# Ethernet.net
KiCad netlist of a schematic drawn in Altium Designer
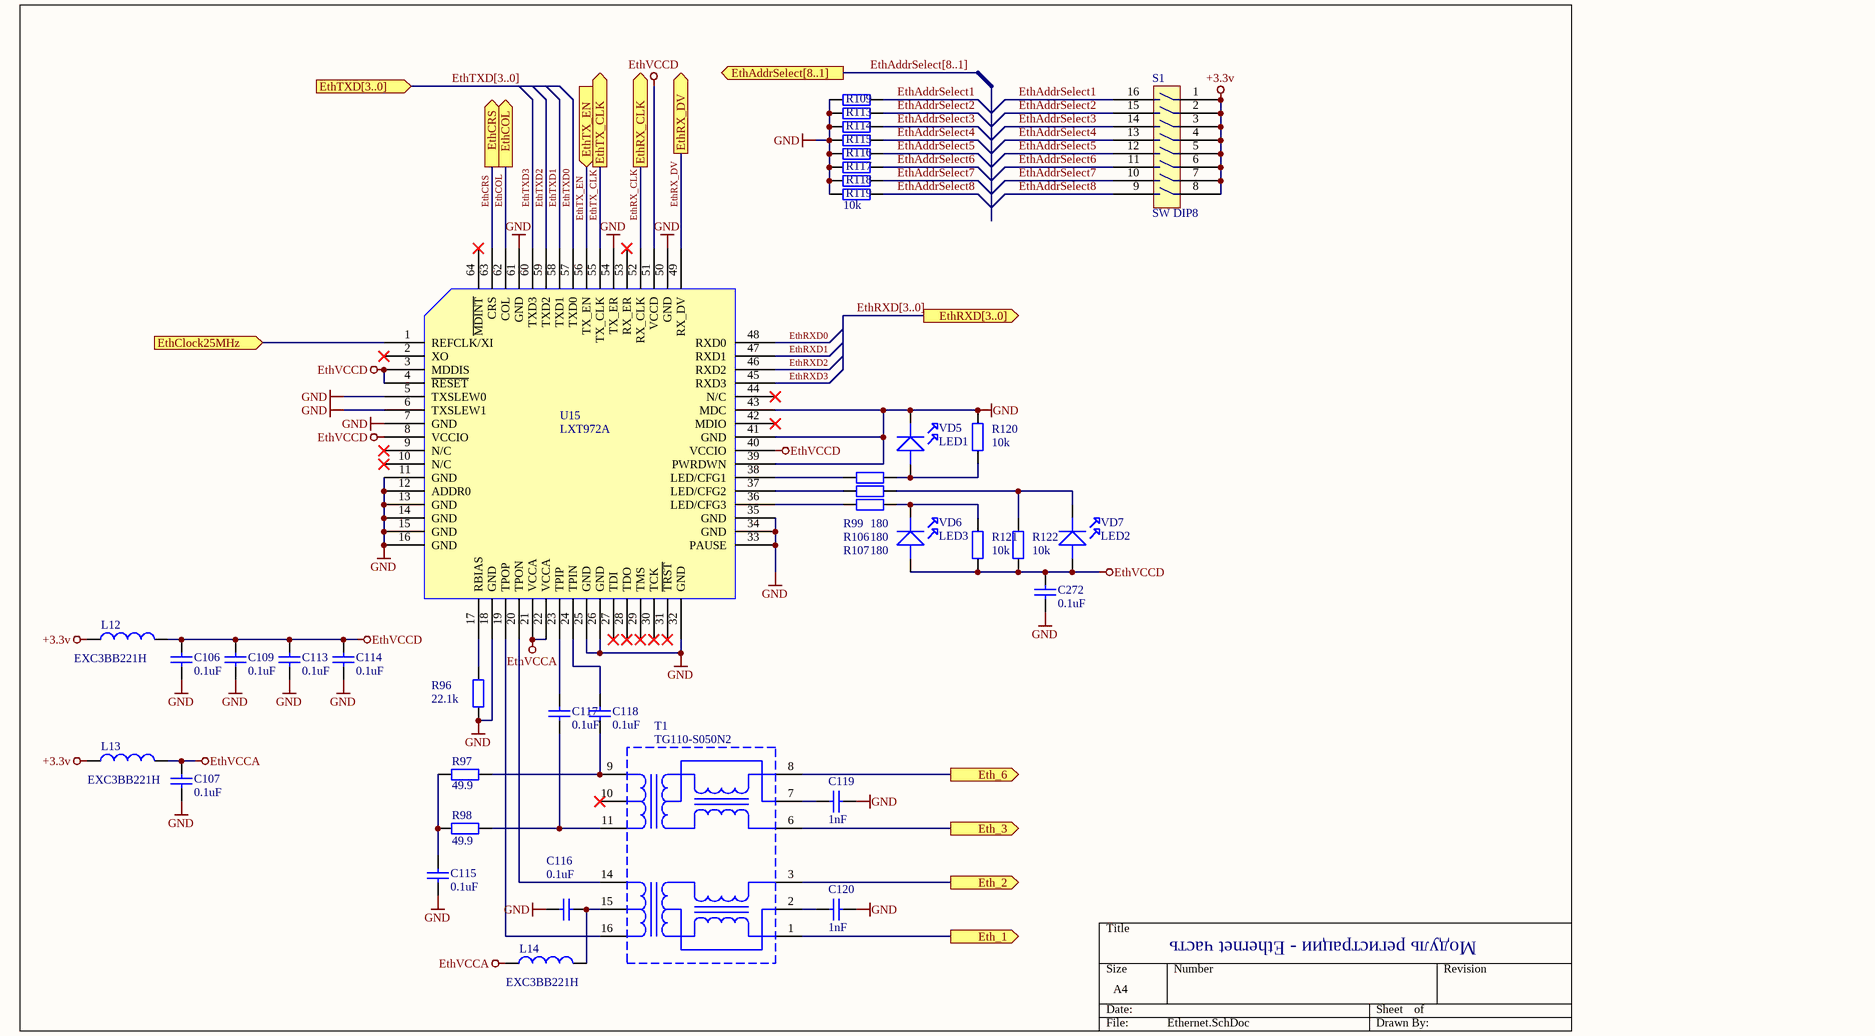
[diagram p0: Ethernet.SchDoc]

(export (version "E")
  (design (tool "Eeschema 10.0.6"))
  (components
    (comp (ref "C106")
      (value "0.1uF")
      (footprint "0603")
      (description "Capacitor")
      (fields (field (name "PUBLISHER") "Altium Limited"))
      (libsource (lib "pcblib1") (part "Cap"))
    )
    (comp (ref "C107")
      (value "0.1uF")
      (footprint "0603")
      (description "Capacitor")
      (fields (field (name "PUBLISHER") "Altium Limited"))
      (libsource (lib "pcblib1") (part "Cap"))
    )
    (comp (ref "C109")
      (value "0.1uF")
      (footprint "0603")
      (description "Capacitor")
      (fields (field (name "PUBLISHER") "Altium Limited"))
      (libsource (lib "pcblib1") (part "Cap"))
    )
    (comp (ref "C113")
      (value "0.1uF")
      (footprint "0603")
      (description "Capacitor")
      (fields (field (name "PUBLISHER") "Altium Limited"))
      (libsource (lib "pcblib1") (part "Cap"))
    )
    (comp (ref "C114")
      (value "0.1uF")
      (footprint "0603")
      (description "Capacitor")
      (fields (field (name "PUBLISHER") "Altium Limited"))
      (libsource (lib "pcblib1") (part "Cap"))
    )
    (comp (ref "C115")
      (value "0.1uF")
      (footprint "0603")
      (description "Capacitor")
      (fields (field (name "PUBLISHER") "Altium Limited"))
      (libsource (lib "pcblib1") (part "Cap"))
    )
    (comp (ref "C116")
      (value "0.1uF")
      (footprint "0603")
      (description "Capacitor")
      (fields (field (name "PUBLISHER") "Altium Limited"))
      (libsource (lib "pcblib1") (part "Cap"))
    )
    (comp (ref "C117")
      (value "0.1uF")
      (footprint "0603")
      (description "Capacitor")
      (fields (field (name "PUBLISHER") "Altium Limited"))
      (libsource (lib "pcblib1") (part "Cap"))
    )
    (comp (ref "C118")
      (value "0.1uF")
      (footprint "0603")
      (description "Capacitor")
      (fields (field (name "PUBLISHER") "Altium Limited"))
      (libsource (lib "pcblib1") (part "Cap"))
    )
    (comp (ref "C119")
      (value "1nF")
      (footprint "0603")
      (description "Capacitor")
      (fields (field (name "PUBLISHER") "Altium Limited"))
      (libsource (lib "pcblib1") (part "Cap"))
    )
    (comp (ref "C120")
      (value "1nF")
      (footprint "0603")
      (description "Capacitor")
      (fields (field (name "PUBLISHER") "Altium Limited"))
      (libsource (lib "pcblib1") (part "Cap"))
    )
    (comp (ref "C272")
      (value "0.1uF")
      (footprint "0603")
      (description "Capacitor")
      (fields (field (name "PUBLISHER") "Altium Limited"))
      (libsource (lib "pcblib1") (part "Cap"))
    )
    (comp (ref "L12") (value "EXC3BB221H") (footprint "0603") (libsource (lib "Adevice") (part "INDUCTOR")))
    (comp (ref "L13") (value "EXC3BB221H") (footprint "0603") (libsource (lib "Adevice") (part "INDUCTOR")))
    (comp (ref "L14") (value "EXC3BB221H") (footprint "0603") (libsource (lib "Adevice") (part "INDUCTOR")))
    (comp (ref "R96")
      (value "22.1k")
      (footprint "0805")
      (description "Resistor")
      (fields (field (name "PUBLISHER") "Altium Limited"))
      (libsource (lib "OD3M") (part "Res2"))
    )
    (comp (ref "R97")
      (value "49.9")
      (footprint "0805")
      (description "Resistor")
      (fields (field (name "PUBLISHER") "Altium Limited"))
      (libsource (lib "") (part "Res2_2"))
    )
    (comp (ref "R98")
      (value "49.9")
      (footprint "0805")
      (description "Resistor")
      (fields (field (name "PUBLISHER") "Altium Limited"))
      (libsource (lib "") (part "Res2_1"))
    )
    (comp (ref "R99")
      (value "180")
      (footprint "0805")
      (description "Resistor")
      (fields (field (name "PUBLISHER") "Altium Limited"))
      (libsource (lib "") (part "Res2_2"))
    )
    (comp (ref "R106")
      (value "180")
      (footprint "0805")
      (description "Resistor")
      (fields (field (name "PUBLISHER") "Altium Limited"))
      (libsource (lib "") (part "Res2_2"))
    )
    (comp (ref "R107")
      (value "180")
      (footprint "0805")
      (description "Resistor")
      (fields (field (name "PUBLISHER") "Altium Limited"))
      (libsource (lib "") (part "Res2_2"))
    )
    (comp (ref "R109")
      (value "10k")
      (footprint "0603")
      (description "Resistor")
      (fields (field (name "PUBLISHER") "Altium Limited"))
      (libsource (lib "") (part "Res2_1"))
    )
    (comp (ref "R113")
      (value "10k")
      (footprint "0603")
      (description "Resistor")
      (fields (field (name "PUBLISHER") "Altium Limited"))
      (libsource (lib "") (part "Res2_1"))
    )
    (comp (ref "R114")
      (value "10k")
      (footprint "0603")
      (description "Resistor")
      (fields (field (name "PUBLISHER") "Altium Limited"))
      (libsource (lib "") (part "Res2_1"))
    )
    (comp (ref "R115")
      (value "10k")
      (footprint "0603")
      (description "Resistor")
      (fields (field (name "PUBLISHER") "Altium Limited"))
      (libsource (lib "") (part "Res2_1"))
    )
    (comp (ref "R116")
      (value "10k")
      (footprint "0603")
      (description "Resistor")
      (fields (field (name "PUBLISHER") "Altium Limited"))
      (libsource (lib "") (part "Res2_1"))
    )
    (comp (ref "R117")
      (value "10k")
      (footprint "0603")
      (description "Resistor")
      (fields (field (name "PUBLISHER") "Altium Limited"))
      (libsource (lib "") (part "Res2_1"))
    )
    (comp (ref "R118")
      (value "10k")
      (footprint "0603")
      (description "Resistor")
      (fields (field (name "PUBLISHER") "Altium Limited"))
      (libsource (lib "") (part "Res2_1"))
    )
    (comp (ref "R119")
      (value "10k")
      (footprint "0603")
      (description "Resistor")
      (fields (field (name "PUBLISHER") "Altium Limited"))
      (libsource (lib "") (part "Res2_1"))
    )
    (comp (ref "R120")
      (value "10k")
      (footprint "0603")
      (description "Resistor")
      (fields (field (name "PUBLISHER") "Altium Limited"))
      (libsource (lib "") (part "Res2_3"))
    )
    (comp (ref "R121")
      (value "10k")
      (footprint "0603")
      (description "Resistor")
      (fields (field (name "PUBLISHER") "Altium Limited"))
      (libsource (lib "") (part "Res2_3"))
    )
    (comp (ref "R122")
      (value "10k")
      (footprint "0603")
      (description "Resistor")
      (fields (field (name "PUBLISHER") "Altium Limited"))
      (libsource (lib "") (part "Res2_3"))
    )
    (comp (ref "S1") (value "SW DIP8") (footprint "SWD4-8") (libsource (lib "Adevice") (part "SW DIP8")))
    (comp (ref "T1")
      (value "TG110-S050N2")
      (footprint "SO-G16/G6.9")
      (libsource (lib "Schlib1") (part "TG110-S050N2"))
    )
    (comp (ref "U15")
      (value "LXT972A")
      (footprint "TQFP64")
      (libsource (lib "MyIntegratedLibrary") (part "LXT972A"))
    )
    (comp (ref "VD5") (value "LED1") (footprint "LED1206") (libsource (lib "Adevice") (part "LED1")))
    (comp (ref "VD6") (value "LED3") (footprint "LED1206") (libsource (lib "Adevice") (part "LED1")))
    (comp (ref "VD7") (value "LED2") (footprint "LED1206") (libsource (lib "Adevice") (part "LED1")))
  )
  (nets
    (net (code "1") (name "+3.3v") (class "Default")
      (node (ref "L12") (pin "1") (pinfunction "1_1") (pintype "passive"))
      (node (ref "L13") (pin "1") (pinfunction "1_1") (pintype "passive"))
      (node (ref "S1") (pin "1") (pinfunction "1_1") (pintype "passive"))
      (node (ref "S1") (pin "2") (pinfunction "2_2") (pintype "passive"))
      (node (ref "S1") (pin "3") (pinfunction "3_3") (pintype "passive"))
      (node (ref "S1") (pin "4") (pinfunction "4_4") (pintype "passive"))
      (node (ref "S1") (pin "5") (pinfunction "5_5") (pintype "passive"))
      (node (ref "S1") (pin "6") (pinfunction "6_6") (pintype "passive"))
      (node (ref "S1") (pin "7") (pinfunction "7_7") (pintype "passive"))
      (node (ref "S1") (pin "8") (pinfunction "8_8") (pintype "passive"))
    )
    (net (code "2") (name "/EthAddrSelect1") (class "Default")
      (node (ref "R109") (pin "1") (pinfunction "1_1") (pintype "passive"))
      (node (ref "S1") (pin "16") (pinfunction "16_16") (pintype "passive"))
    )
    (net (code "3") (name "/EthAddrSelect2") (class "Default")
      (node (ref "R113") (pin "1") (pinfunction "1_1") (pintype "passive"))
      (node (ref "S1") (pin "15") (pinfunction "15_15") (pintype "passive"))
    )
    (net (code "4") (name "/EthAddrSelect3") (class "Default")
      (node (ref "R114") (pin "1") (pinfunction "1_1") (pintype "passive"))
      (node (ref "S1") (pin "14") (pinfunction "14_14") (pintype "passive"))
    )
    (net (code "5") (name "/EthAddrSelect4") (class "Default")
      (node (ref "R115") (pin "1") (pinfunction "1_1") (pintype "passive"))
      (node (ref "S1") (pin "13") (pinfunction "13_13") (pintype "passive"))
    )
    (net (code "6") (name "/EthAddrSelect5") (class "Default")
      (node (ref "R116") (pin "1") (pinfunction "1_1") (pintype "passive"))
      (node (ref "S1") (pin "12") (pinfunction "12_12") (pintype "passive"))
    )
    (net (code "7") (name "/EthAddrSelect6") (class "Default")
      (node (ref "R117") (pin "1") (pinfunction "1_1") (pintype "passive"))
      (node (ref "S1") (pin "11") (pinfunction "11_11") (pintype "passive"))
    )
    (net (code "8") (name "/EthAddrSelect7") (class "Default")
      (node (ref "R118") (pin "1") (pinfunction "1_1") (pintype "passive"))
      (node (ref "S1") (pin "10") (pinfunction "10_10") (pintype "passive"))
    )
    (net (code "9") (name "/EthAddrSelect8") (class "Default")
      (node (ref "R119") (pin "1") (pinfunction "1_1") (pintype "passive"))
      (node (ref "S1") (pin "9") (pinfunction "9_9") (pintype "passive"))
    )
    (net (code "11") (name "/EthCOL") (class "Default")
      (node (ref "U15") (pin "62") (pinfunction "COL_62") (pintype "passive"))
    )
    (net (code "12") (name "/EthCRS") (class "Default")
      (node (ref "U15") (pin "63") (pinfunction "CRS_63") (pintype "passive"))
    )
    (net (code "13") (name "/EthClock25MHz") (class "Default")
      (node (ref "U15") (pin "1") (pinfunction "REFCLK/XI_1") (pintype "passive"))
    )
    (net (code "14") (name "/EthRXD0") (class "Default")
      (node (ref "U15") (pin "48") (pinfunction "RXD0_48") (pintype "passive"))
    )
    (net (code "15") (name "/EthRXD1") (class "Default")
      (node (ref "U15") (pin "47") (pinfunction "RXD1_47") (pintype "passive"))
    )
    (net (code "16") (name "/EthRXD2") (class "Default")
      (node (ref "U15") (pin "46") (pinfunction "RXD2_46") (pintype "passive"))
    )
    (net (code "17") (name "/EthRXD3") (class "Default")
      (node (ref "U15") (pin "45") (pinfunction "RXD3_45") (pintype "passive"))
    )
    (net (code "19") (name "/EthRX_CLK") (class "Default")
      (node (ref "U15") (pin "52") (pinfunction "RX_CLK_52") (pintype "passive"))
    )
    (net (code "20") (name "/EthRX_DV") (class "Default")
      (node (ref "U15") (pin "49") (pinfunction "RX_DV_49") (pintype "passive"))
    )
    (net (code "21") (name "/EthTXD0") (class "Default")
      (node (ref "U15") (pin "57") (pinfunction "TXD0_57") (pintype "passive"))
    )
    (net (code "22") (name "/EthTXD1") (class "Default")
      (node (ref "U15") (pin "58") (pinfunction "TXD1_58") (pintype "passive"))
    )
    (net (code "23") (name "/EthTXD2") (class "Default")
      (node (ref "U15") (pin "59") (pinfunction "TXD2_59") (pintype "passive"))
    )
    (net (code "24") (name "/EthTXD3") (class "Default")
      (node (ref "U15") (pin "60") (pinfunction "TXD3_60") (pintype "passive"))
    )
    (net (code "26") (name "/EthTX_CLK") (class "Default")
      (node (ref "U15") (pin "55") (pinfunction "TX_CLK_55") (pintype "passive"))
    )
    (net (code "27") (name "/EthTX_EN") (class "Default")
      (node (ref "U15") (pin "56") (pinfunction "TX_EN_56") (pintype "passive"))
    )
    (net (code "28") (name "/Eth_1") (class "Default") (node (ref "T1") (pin "1") (pintype "passive")))
    (net (code "29") (name "/Eth_2") (class "Default") (node (ref "T1") (pin "3") (pintype "passive")))
    (net (code "30") (name "/Eth_3") (class "Default") (node (ref "T1") (pin "6") (pintype "passive")))
    (net (code "31") (name "/Eth_6") (class "Default") (node (ref "T1") (pin "8") (pintype "passive")))
    (net (code "32") (name "EthVCCA") (class "Default")
      (node (ref "C107") (pin "2") (pinfunction "2_2") (pintype "passive"))
      (node (ref "L13") (pin "2") (pinfunction "2_2") (pintype "passive"))
      (node (ref "L14") (pin "1") (pinfunction "1_1") (pintype "passive"))
      (node (ref "U15") (pin "21") (pinfunction "VCCA_21") (pintype "passive"))
      (node (ref "U15") (pin "22") (pinfunction "VCCA_22") (pintype "passive"))
    )
    (net (code "33") (name "EthVCCD") (class "Default")
      (node (ref "C106") (pin "2") (pinfunction "2_2") (pintype "passive"))
      (node (ref "C109") (pin "2") (pinfunction "2_2") (pintype "passive"))
      (node (ref "C113") (pin "2") (pinfunction "2_2") (pintype "passive"))
      (node (ref "C114") (pin "2") (pinfunction "2_2") (pintype "passive"))
      (node (ref "C272") (pin "2") (pinfunction "2_2") (pintype "passive"))
      (node (ref "L12") (pin "2") (pinfunction "2_2") (pintype "passive"))
      (node (ref "R121") (pin "1") (pinfunction "1_1") (pintype "passive"))
      (node (ref "R122") (pin "1") (pinfunction "1_1") (pintype "passive"))
      (node (ref "U15") (pin "3") (pinfunction "MDDIS_3") (pintype "passive"))
      (node (ref "U15") (pin "4") (pinfunction "RESET_4") (pintype "passive"))
      (node (ref "U15") (pin "40") (pinfunction "VCCIO_40") (pintype "passive"))
      (node (ref "U15") (pin "51") (pinfunction "VCCD_51") (pintype "passive"))
      (node (ref "U15") (pin "8") (pinfunction "VCCIO_8") (pintype "passive"))
      (node (ref "VD6") (pin "ANODE") (pinfunction "ANODE_ANODE") (pintype "passive"))
      (node (ref "VD7") (pin "ANODE") (pinfunction "ANODE_ANODE") (pintype "passive"))
    )
    (net (code "34") (name "GND") (class "Default")
      (node (ref "C106") (pin "1") (pinfunction "1_1") (pintype "passive"))
      (node (ref "C107") (pin "1") (pinfunction "1_1") (pintype "passive"))
      (node (ref "C109") (pin "1") (pinfunction "1_1") (pintype "passive"))
      (node (ref "C113") (pin "1") (pinfunction "1_1") (pintype "passive"))
      (node (ref "C114") (pin "1") (pinfunction "1_1") (pintype "passive"))
      (node (ref "C115") (pin "2") (pinfunction "2_2") (pintype "passive"))
      (node (ref "C116") (pin "1") (pinfunction "1_1") (pintype "passive"))
      (node (ref "C119") (pin "2") (pinfunction "2_2") (pintype "passive"))
      (node (ref "C120") (pin "1") (pinfunction "1_1") (pintype "passive"))
      (node (ref "C272") (pin "1") (pinfunction "1_1") (pintype "passive"))
      (node (ref "R109") (pin "2") (pinfunction "2_2") (pintype "passive"))
      (node (ref "R113") (pin "2") (pinfunction "2_2") (pintype "passive"))
      (node (ref "R114") (pin "2") (pinfunction "2_2") (pintype "passive"))
      (node (ref "R115") (pin "2") (pinfunction "2_2") (pintype "passive"))
      (node (ref "R116") (pin "2") (pinfunction "2_2") (pintype "passive"))
      (node (ref "R117") (pin "2") (pinfunction "2_2") (pintype "passive"))
      (node (ref "R118") (pin "2") (pinfunction "2_2") (pintype "passive"))
      (node (ref "R119") (pin "2") (pinfunction "2_2") (pintype "passive"))
      (node (ref "R120") (pin "2") (pinfunction "2_2") (pintype "passive"))
      (node (ref "R96") (pin "2") (pinfunction "2_2") (pintype "passive"))
      (node (ref "U15") (pin "11") (pinfunction "GND_11") (pintype "passive"))
      (node (ref "U15") (pin "12") (pinfunction "ADDR0_12") (pintype "passive"))
      (node (ref "U15") (pin "13") (pinfunction "GND_13") (pintype "passive"))
      (node (ref "U15") (pin "14") (pinfunction "GND_14") (pintype "passive"))
      (node (ref "U15") (pin "15") (pinfunction "GND_15") (pintype "passive"))
      (node (ref "U15") (pin "16") (pinfunction "GND_16") (pintype "passive"))
      (node (ref "U15") (pin "18") (pinfunction "GND_18") (pintype "passive"))
      (node (ref "U15") (pin "25") (pinfunction "GND_25") (pintype "passive"))
      (node (ref "U15") (pin "26") (pinfunction "GND_26") (pintype "passive"))
      (node (ref "U15") (pin "32") (pinfunction "GND_32") (pintype "passive"))
      (node (ref "U15") (pin "33") (pinfunction "PAUSE_33") (pintype "passive"))
      (node (ref "U15") (pin "34") (pinfunction "GND_34") (pintype "passive"))
      (node (ref "U15") (pin "35") (pinfunction "GND_35") (pintype "passive"))
      (node (ref "U15") (pin "39") (pinfunction "PWRDWN_39") (pintype "passive"))
      (node (ref "U15") (pin "41") (pinfunction "GND_41") (pintype "passive"))
      (node (ref "U15") (pin "43") (pinfunction "MDC_43") (pintype "passive"))
      (node (ref "U15") (pin "5") (pinfunction "TXSLEW0_5") (pintype "passive"))
      (node (ref "U15") (pin "50") (pinfunction "GND_50") (pintype "passive"))
      (node (ref "U15") (pin "54") (pinfunction "TX_ER_54") (pintype "passive"))
      (node (ref "U15") (pin "6") (pinfunction "TXSLEW1_6") (pintype "passive"))
      (node (ref "U15") (pin "61") (pinfunction "GND_61") (pintype "passive"))
      (node (ref "U15") (pin "7") (pinfunction "GND_7") (pintype "passive"))
      (node (ref "VD5") (pin "CATHODE") (pinfunction "CATHODE_CATHODE") (pintype "passive"))
    )
    (net (code "35") (name "Net-(C115-Pad1)") (class "Default")
      (node (ref "C115") (pin "1") (pinfunction "1_1") (pintype "passive"))
      (node (ref "R97") (pin "1") (pinfunction "1_1") (pintype "passive"))
      (node (ref "R98") (pin "2") (pinfunction "2_2") (pintype "passive"))
    )
    (net (code "36") (name "Net-(C116-Pad2)") (class "Default")
      (node (ref "C116") (pin "2") (pinfunction "2_2") (pintype "passive"))
      (node (ref "L14") (pin "2") (pinfunction "2_2") (pintype "passive"))
      (node (ref "T1") (pin "15") (pintype "passive"))
    )
    (net (code "37") (name "Net-(C117-Pad1)") (class "Default")
      (node (ref "C117") (pin "1") (pinfunction "1_1") (pintype "passive"))
      (node (ref "R98") (pin "1") (pinfunction "1_1") (pintype "passive"))
      (node (ref "T1") (pin "11") (pintype "passive"))
    )
    (net (code "38") (name "Net-(C118-Pad1)") (class "Default")
      (node (ref "C118") (pin "1") (pinfunction "1_1") (pintype "passive"))
      (node (ref "R97") (pin "2") (pinfunction "2_2") (pintype "passive"))
      (node (ref "T1") (pin "9") (pintype "passive"))
    )
    (net (code "39") (name "Net-(C119-Pad1)") (class "Default")
      (node (ref "C119") (pin "1") (pinfunction "1_1") (pintype "passive"))
      (node (ref "T1") (pin "7") (pintype "passive"))
    )
    (net (code "40") (name "Net-(C120-Pad2)") (class "Default")
      (node (ref "C120") (pin "2") (pinfunction "2_2") (pintype "passive"))
      (node (ref "T1") (pin "2") (pintype "passive"))
    )
    (net (code "41") (name "Net-(R106-Pad2)") (class "Default")
      (node (ref "R106") (pin "2") (pinfunction "2_2") (pintype "passive"))
      (node (ref "R122") (pin "2") (pinfunction "2_2") (pintype "passive"))
      (node (ref "VD7") (pin "CATHODE") (pinfunction "CATHODE_CATHODE") (pintype "passive"))
    )
    (net (code "42") (name "Net-(R107-Pad2)") (class "Default")
      (node (ref "R107") (pin "2") (pinfunction "2_2") (pintype "passive"))
      (node (ref "R121") (pin "2") (pinfunction "2_2") (pintype "passive"))
      (node (ref "VD6") (pin "CATHODE") (pinfunction "CATHODE_CATHODE") (pintype "passive"))
    )
    (net (code "43") (name "Net-(R120-Pad1)") (class "Default")
      (node (ref "R120") (pin "1") (pinfunction "1_1") (pintype "passive"))
      (node (ref "R99") (pin "2") (pinfunction "2_2") (pintype "passive"))
      (node (ref "VD5") (pin "ANODE") (pinfunction "ANODE_ANODE") (pintype "passive"))
    )
    (net (code "44") (name "Net-(U15-LED{slash}CFG1)") (class "Default")
      (node (ref "R99") (pin "1") (pinfunction "1_1") (pintype "passive"))
      (node (ref "U15") (pin "38") (pinfunction "LED/CFG1_38") (pintype "passive"))
    )
    (net (code "45") (name "Net-(U15-LED{slash}CFG2)") (class "Default")
      (node (ref "R106") (pin "1") (pinfunction "1_1") (pintype "passive"))
      (node (ref "U15") (pin "37") (pinfunction "LED/CFG2_37") (pintype "passive"))
    )
    (net (code "46") (name "Net-(U15-LED{slash}CFG3)") (class "Default")
      (node (ref "R107") (pin "1") (pinfunction "1_1") (pintype "passive"))
      (node (ref "U15") (pin "36") (pinfunction "LED/CFG3_36") (pintype "passive"))
    )
    (net (code "47") (name "Net-(U15-RBIAS)") (class "Default")
      (node (ref "R96") (pin "1") (pinfunction "1_1") (pintype "passive"))
      (node (ref "U15") (pin "17") (pinfunction "RBIAS_17") (pintype "passive"))
    )
    (net (code "48") (name "Net-(U15-TPIN)") (class "Default")
      (node (ref "C118") (pin "2") (pinfunction "2_2") (pintype "passive"))
      (node (ref "U15") (pin "24") (pinfunction "TPIN_24") (pintype "passive"))
    )
    (net (code "49") (name "Net-(U15-TPIP)") (class "Default")
      (node (ref "C117") (pin "2") (pinfunction "2_2") (pintype "passive"))
      (node (ref "U15") (pin "23") (pinfunction "TPIP_23") (pintype "passive"))
    )
    (net (code "50") (name "Net-(U15-TPON)") (class "Default")
      (node (ref "T1") (pin "14") (pintype "passive"))
      (node (ref "U15") (pin "20") (pinfunction "TPON_20") (pintype "passive"))
    )
    (net (code "51") (name "Net-(U15-TPOP)") (class "Default")
      (node (ref "T1") (pin "16") (pintype "passive"))
      (node (ref "U15") (pin "19") (pinfunction "TPOP_19") (pintype "passive"))
    )
    (net (code "52") (name "unconnected-(T1-Pad10)") (class "Default")
      (node (ref "T1") (pin "10") (pintype "passive+no_connect"))
    )
    (net (code "53") (name "unconnected-(U15-MDINT-Pad64)") (class "Default")
      (node (ref "U15") (pin "64") (pinfunction "MDINT_64") (pintype "passive+no_connect"))
    )
    (net (code "54") (name "unconnected-(U15-MDIO-Pad42)") (class "Default")
      (node (ref "U15") (pin "42") (pinfunction "MDIO_42") (pintype "passive+no_connect"))
    )
    (net (code "55") (name "unconnected-(U15-N{slash}C-Pad9)") (class "Default")
      (node (ref "U15") (pin "9") (pinfunction "N/C_9") (pintype "passive+no_connect"))
    )
    (net (code "56") (name "unconnected-(U15-N{slash}C-Pad10)") (class "Default")
      (node (ref "U15") (pin "10") (pinfunction "N/C_10") (pintype "passive+no_connect"))
    )
    (net (code "57") (name "unconnected-(U15-N{slash}C-Pad44)") (class "Default")
      (node (ref "U15") (pin "44") (pinfunction "N/C_44") (pintype "passive+no_connect"))
    )
    (net (code "58") (name "unconnected-(U15-RX_ER-Pad53)") (class "Default")
      (node (ref "U15") (pin "53") (pinfunction "RX_ER_53") (pintype "passive+no_connect"))
    )
    (net (code "59") (name "unconnected-(U15-TCK-Pad30)") (class "Default")
      (node (ref "U15") (pin "30") (pinfunction "TCK_30") (pintype "passive+no_connect"))
    )
    (net (code "60") (name "unconnected-(U15-TDI-Pad27)") (class "Default")
      (node (ref "U15") (pin "27") (pinfunction "TDI_27") (pintype "passive+no_connect"))
    )
    (net (code "61") (name "unconnected-(U15-TDO-Pad28)") (class "Default")
      (node (ref "U15") (pin "28") (pinfunction "TDO_28") (pintype "passive+no_connect"))
    )
    (net (code "62") (name "unconnected-(U15-TMS-Pad29)") (class "Default")
      (node (ref "U15") (pin "29") (pinfunction "TMS_29") (pintype "passive+no_connect"))
    )
    (net (code "63") (name "unconnected-(U15-TRST-Pad31)") (class "Default")
      (node (ref "U15") (pin "31") (pinfunction "TRST_31") (pintype "passive+no_connect"))
    )
    (net (code "64") (name "unconnected-(U15-XO-Pad2)") (class "Default")
      (node (ref "U15") (pin "2") (pinfunction "XO_2") (pintype "passive+no_connect"))
    )
  )
)
